# E-14_ENET1.net
KiCad netlist of a schematic drawn in Altium Designer
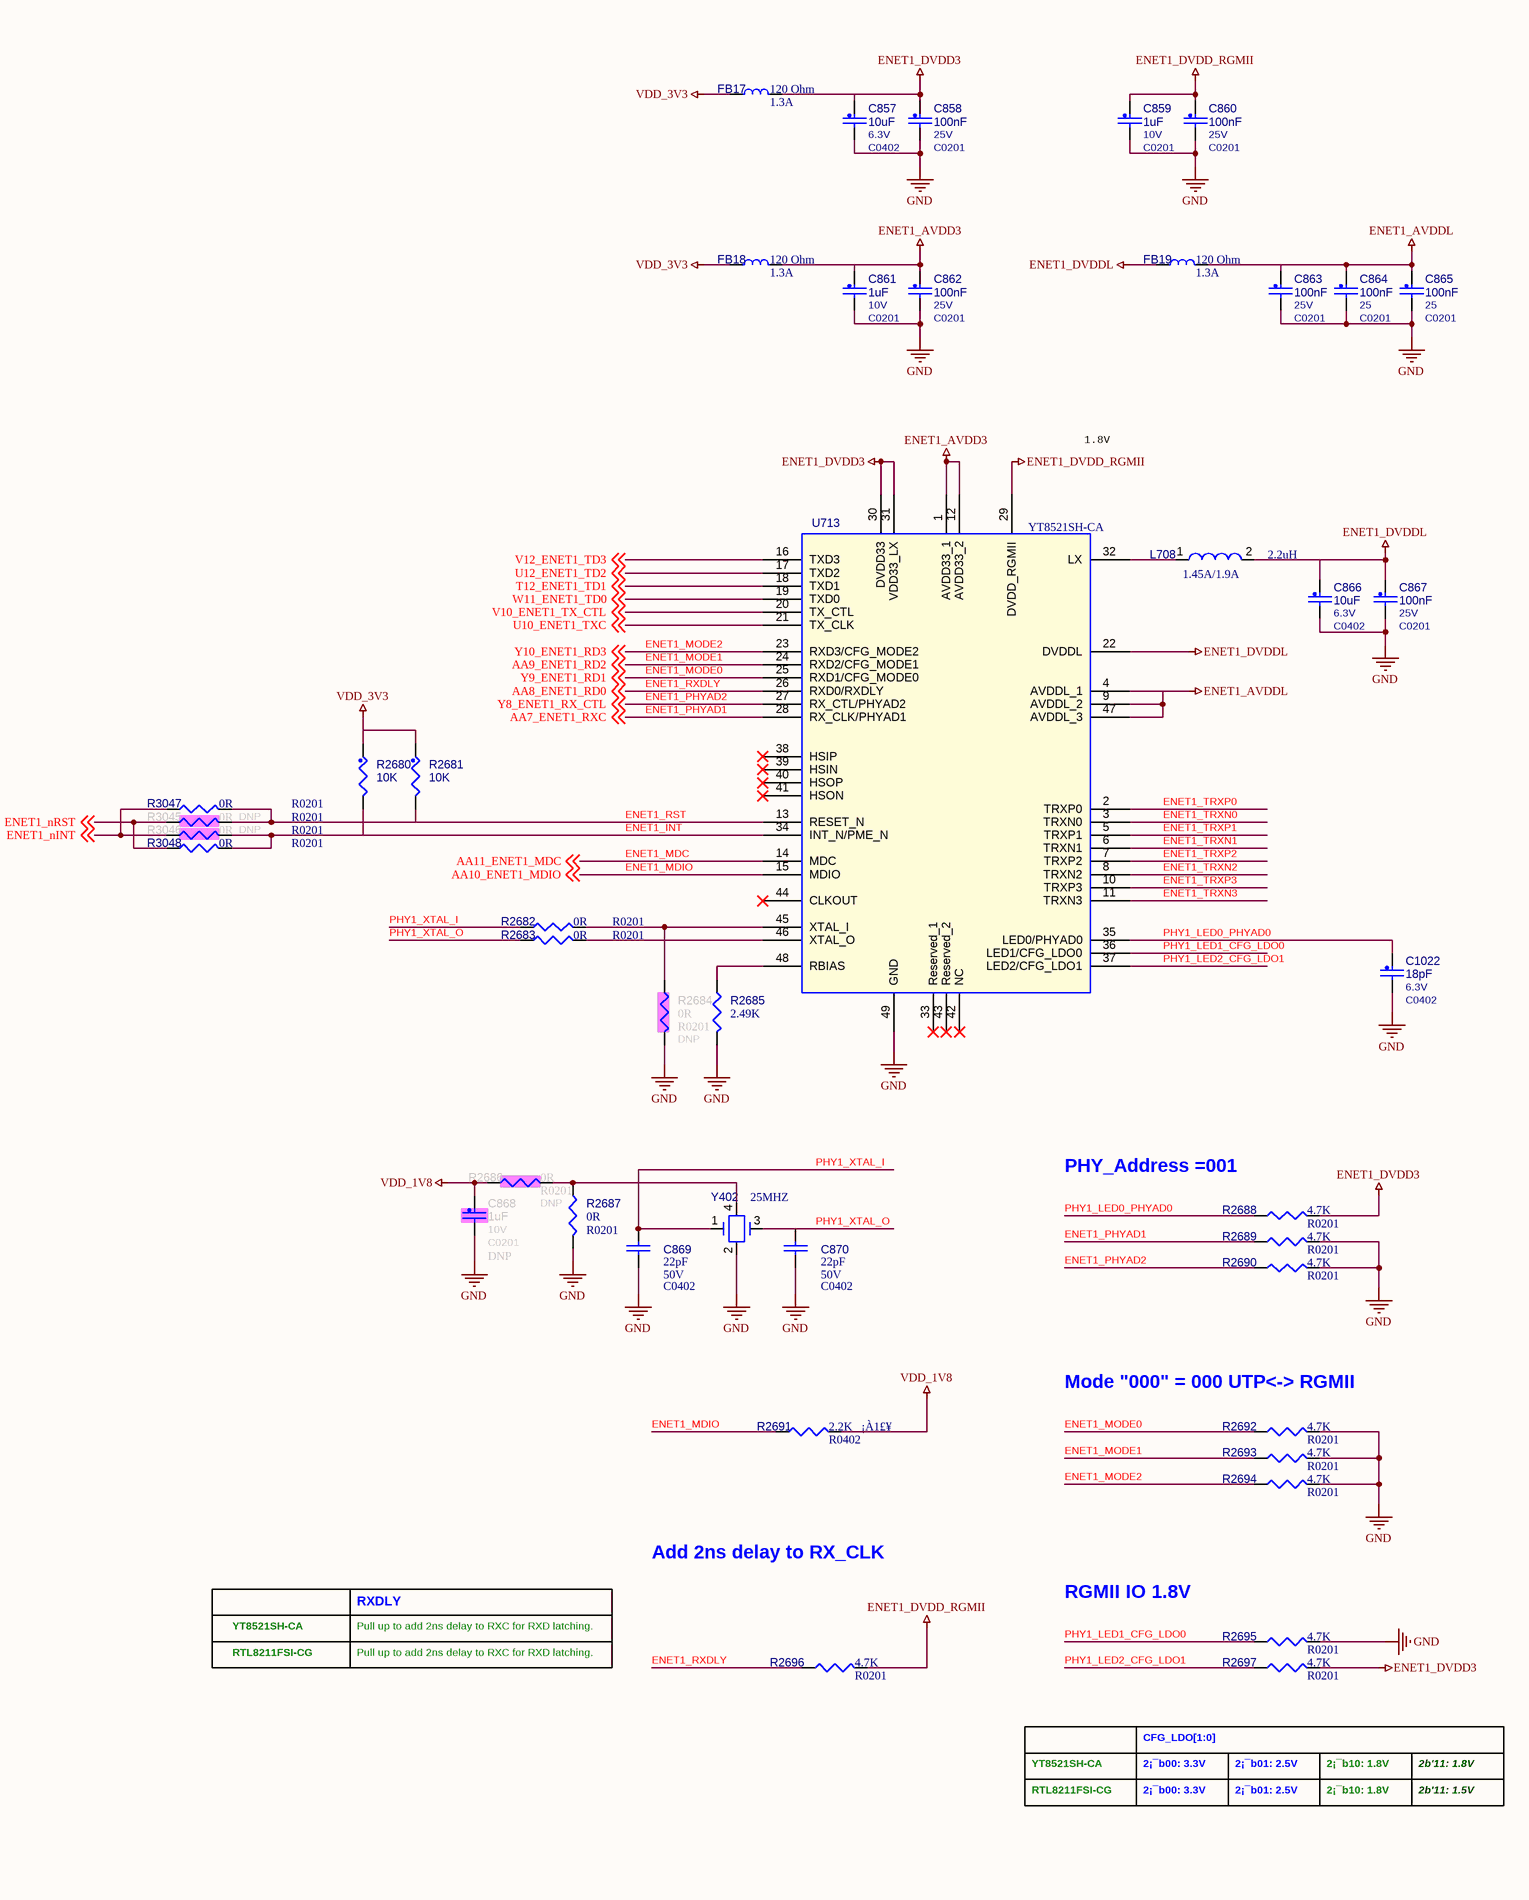
[diagram p0: E-14 ENET1.SchDoc, left]
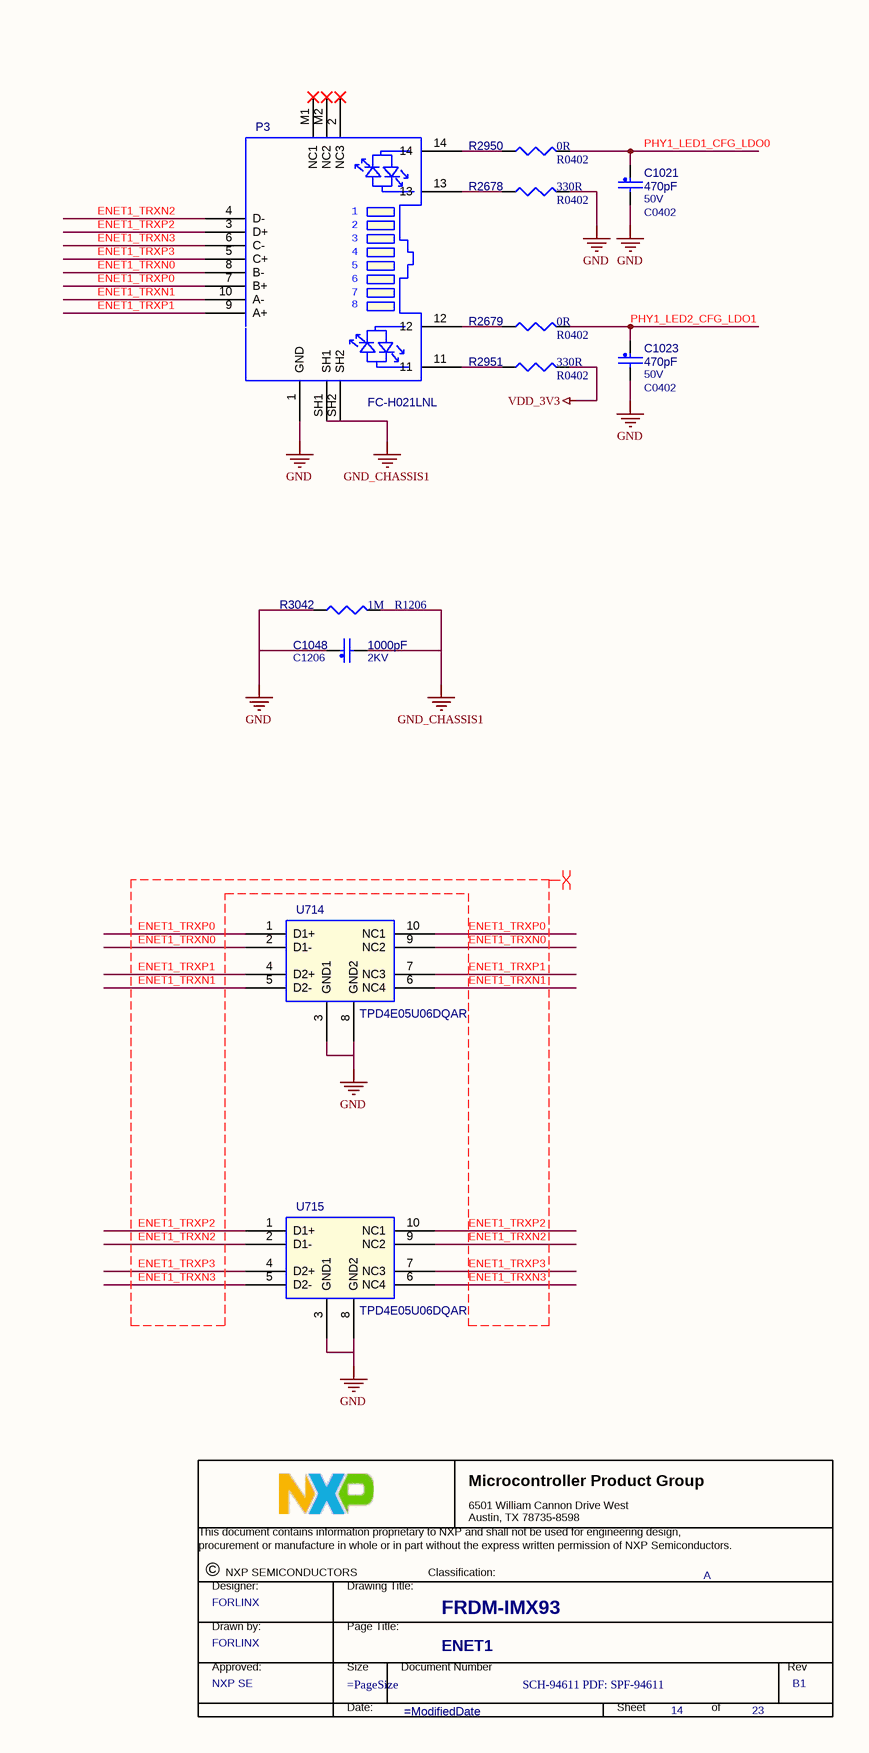
[diagram p1: E-14 ENET1.SchDoc, right]

(export (version "E")
  (design (tool "Eeschema 10.0.6"))
  (components
    (comp (ref "C857")
      (value "10uF")
      (footprint "C0402")
      (description "0402,10uF,6.3V,+/-20%,X5R")
      (fields
        (field (name "TOLERANCE") "20%")
        (field (name "VOLTAGE") "6.3V")
        (field (name "PCB FOOTPRINT") "C0402")
      )
      (libsource (lib "*") (part "CAP_NP"))
    )
    (comp (ref "C858")
      (value "100nF")
      (footprint "C0201")
      (description "0201,100nF,25V,+/-10%,X5R")
      (fields
        (field (name "VOLTAGE") "25V")
        (field (name "TOLERANCE") "20%")
        (field (name "PCB FOOTPRINT") "C0201")
      )
      (libsource (lib "*") (part "CAP_NP"))
    )
    (comp (ref "C859")
      (value "1uF")
      (footprint "C0201")
      (description "0201,1uF,10V,+/-20%,X5R")
      (fields
        (field (name "VOLTAGE") "10V")
        (field (name "TOLERANCE") "20%")
        (field (name "PCB FOOTPRINT") "C0201")
      )
      (libsource (lib "*") (part "CAP_NP"))
    )
    (comp (ref "C860")
      (value "100nF")
      (footprint "C0201")
      (description "0201,100nF,25V,+/-10%,X5R")
      (fields
        (field (name "TOLERANCE") "20%")
        (field (name "VOLTAGE") "25V")
        (field (name "PCB FOOTPRINT") "C0201")
      )
      (libsource (lib "*") (part "CAP_NP"))
    )
    (comp (ref "C861")
      (value "1uF")
      (footprint "C0201")
      (description "0201,1uF,10V,+/-20%,X5R")
      (fields
        (field (name "TOLERANCE") "20%")
        (field (name "VOLTAGE") "10V")
        (field (name "PCB FOOTPRINT") "C0201")
      )
      (libsource (lib "*") (part "CAP_NP"))
    )
    (comp (ref "C862")
      (value "100nF")
      (footprint "C0201")
      (description "0201,100nF,25V,+/-10%,X5R")
      (fields
        (field (name "TOLERANCE") "20%")
        (field (name "VOLTAGE") "25V")
        (field (name "PCB FOOTPRINT") "C0201")
      )
      (libsource (lib "*") (part "CAP_NP"))
    )
    (comp (ref "C863")
      (value "100nF")
      (footprint "C0201")
      (description "0201,100nF,25V,+/-10%,X5R")
      (fields
        (field (name "VOLTAGE") "25V")
        (field (name "TOLERANCE") "20%")
        (field (name "PCB FOOTPRINT") "C0201")
      )
      (libsource (lib "*") (part "CAP_NP"))
    )
    (comp (ref "C864")
      (value "100nF")
      (footprint "C0201")
      (description "0201,100nF,25V,+/-10%,X5R")
      (fields
        (field (name "VOLTAGE") "25")
        (field (name "TOLERANCE") "20%")
        (field (name "PCB FOOTPRINT") "C0201")
      )
      (libsource (lib "*") (part "CAP_NP"))
    )
    (comp (ref "C865")
      (value "100nF")
      (footprint "C0201")
      (description "0201,100nF,25V,+/-10%,X5R")
      (fields
        (field (name "TOLERANCE") "20%")
        (field (name "VOLTAGE") "25")
        (field (name "PCB FOOTPRINT") "C0201")
      )
      (libsource (lib "*") (part "CAP_NP"))
    )
    (comp (ref "C866")
      (value "10uF")
      (footprint "C0402")
      (description "0402,10uF,6.3V,+/-20%,X5R")
      (fields
        (field (name "VOLTAGE") "6.3V")
        (field (name "TOLERANCE") "20%")
        (field (name "PCB FOOTPRINT") "C0402")
      )
      (libsource (lib "*") (part "CAP_NP"))
    )
    (comp (ref "C867")
      (value "100nF")
      (footprint "C0201")
      (description "0201,100nF,25V,+/-10%,X5R")
      (fields
        (field (name "TOLERANCE") "20%")
        (field (name "VOLTAGE") "25V")
        (field (name "PCB FOOTPRINT") "C0201")
      )
      (libsource (lib "*") (part "CAP_NP"))
    )
    (comp (ref "C868")
      (value "1uF")
      (footprint "C0201")
      (description "0201,1uF,10V,+/-20%,X5R")
      (fields
        (field (name "ASSY_OPT") "DNP")
        (field (name "TOLERANCE") "20%")
        (field (name "VOLTAGE") "10V")
        (field (name "PCB FOOTPRINT") "C0201")
      )
      (libsource (lib "*") (part "CAP_NP"))
    )
    (comp (ref "C869")
      (value "22pF")
      (footprint "C0402")
      (description "0402,22pF,50V,+/-5%,NPO")
      (fields (field (name "PCB FOOTPRINT") "C0402") (field (name "VOLTAGE") "50V"))
      (libsource (lib "*") (part "C0402,22pF"))
    )
    (comp (ref "C870")
      (value "22pF")
      (footprint "C0402")
      (description "0402,22pF,50V,+/-5%,NPO")
      (fields (field (name "PCB FOOTPRINT") "C0402") (field (name "VOLTAGE") "50V"))
      (libsource (lib "*") (part "C0402,22pF"))
    )
    (comp (ref "C1021")
      (value "470pF")
      (footprint "C0402")
      (description "0402,470pF,50V,+/-5%,NPO")
      (fields
        (field (name "VOLTAGE") "50V")
        (field (name "TOLERANCE") "20%")
        (field (name "PCB FOOTPRINT") "C0402")
      )
      (libsource (lib "*") (part "CAP_NP"))
    )
    (comp (ref "C1022")
      (value "18pF")
      (footprint "C0402")
      (description "0402,18pF,50V,+/-5%,NPO")
      (fields
        (field (name "TOLERANCE") "20%")
        (field (name "VOLTAGE") "6.3V")
        (field (name "PCB FOOTPRINT") "C0402")
      )
      (libsource (lib "*") (part "CAP_NP"))
    )
    (comp (ref "C1023")
      (value "470pF")
      (footprint "C0402")
      (description "0402,470pF,50V,+/-5%,NPO")
      (fields
        (field (name "VOLTAGE") "50V")
        (field (name "TOLERANCE") "20%")
        (field (name "PCB FOOTPRINT") "C0402")
      )
      (libsource (lib "*") (part "CAP_NP"))
    )
    (comp (ref "C1048")
      (value "1000pF")
      (footprint "C1206")
      (description "1206,1nF,2KV,+/-10%")
      (fields
        (field (name "TOLERANCE") "20%")
        (field (name "VOLTAGE") "2KV")
        (field (name "PCB FOOTPRINT") "C1206")
      )
      (libsource (lib "*") (part "CAP_NP"))
    )
    (comp (ref "FB17")
      (value "120 Ohm")
      (footprint "FB0402")
      (description "0402,120Ohm@100MHz,2A")
      (fields (field (name "ELECTRIC CURRENT") "1.3A"))
      (libsource (lib "*") (part "FB0402,120ohm,1.3A"))
    )
    (comp (ref "FB18")
      (value "120 Ohm")
      (footprint "FB0402")
      (description "0402,120Ohm@100MHz,2A")
      (fields (field (name "ELECTRIC CURRENT") "1.3A"))
      (libsource (lib "*") (part "FB0402,120ohm,1.3A"))
    )
    (comp (ref "FB19")
      (value "120 Ohm")
      (footprint "FB0402")
      (description "0402,120Ohm@100MHz,2A")
      (fields (field (name "ELECTRIC CURRENT") "1.3A"))
      (libsource (lib "*") (part "FB0402,120ohm,1.3A"))
    )
    (comp (ref "L708")
      (value "2.2uH")
      (footprint "IND_2016A")
      (description "2.2uH,2*1.6*1mm,2.15A")
      (fields (field (name "ELECTRIC CURRENT") "1.45A/1.9A"))
      (libsource (lib "*") (part "INDUCTOR-WPN201612HR47MT"))
    )
    (comp (ref "P3")
      (value "FC-H021LNL")
      (footprint "RJ45-Gigabit")
      (description "HR851178A,RJ45,1000M")
      (libsource (lib "*") (part "FC-H021LNL_2"))
    )
    (comp (ref "R2678")
      (value "330R")
      (footprint "R0402")
      (description "0402,330Ohm,+/-1%")
      (fields (field (name "PCB FOOTPRINT") "R0402"))
      (libsource (lib "*") (part "R0402,4.7K_Dup1"))
    )
    (comp (ref "R2679")
      (value "0R")
      (footprint "R0402")
      (description "0402,0Ohm,+/-1%")
      (fields (field (name "PCB FOOTPRINT") "R0402"))
      (libsource (lib "*") (part "R0402,4.7K_Dup1"))
    )
    (comp (ref "R2680")
      (value "10K")
      (footprint "R0201")
      (description "0201,10K,+/-5%")
      (fields (field (name "TOLERANCE") "5%"))
      (libsource (lib "*") (part "RES"))
    )
    (comp (ref "R2681")
      (value "10K")
      (footprint "R0201")
      (description "0201,10K,+/-5%")
      (fields (field (name "TOLERANCE") "5%"))
      (libsource (lib "*") (part "RES"))
    )
    (comp (ref "R2682")
      (value "0R")
      (footprint "R0201")
      (description "0201,0Ohm,+/-5%")
      (fields (field (name "PCB FOOTPRINT") "R0201"))
      (libsource (lib "*") (part "R0402,1.5K"))
    )
    (comp (ref "R2683")
      (value "0R")
      (footprint "R0201")
      (description "0201,0Ohm,+/-5%")
      (fields (field (name "PCB FOOTPRINT") "R0201"))
      (libsource (lib "*") (part "R0402,1.5K"))
    )
    (comp (ref "R2684")
      (value "0R")
      (footprint "R0201")
      (description "0201,0Ohm,+/-5%")
      (fields (field (name "PCB FOOTPRINT") "R0201") (field (name "ASSY_OPT") "DNP"))
      (libsource (lib "*") (part "R0402,1.5K"))
    )
    (comp (ref "R2685")
      (value "2.49K")
      (footprint "R0402")
      (description "0402,2.49K,+/-1%")
      (libsource (lib "*") (part "R0402,2.49K"))
    )
    (comp (ref "R2686")
      (value "0R")
      (footprint "R0201")
      (description "0201,0Ohm,+/-5%")
      (fields (field (name "PCB FOOTPRINT") "R0201") (field (name "ASSY_OPT") "DNP"))
      (libsource (lib "*") (part "R0402,1.5K"))
    )
    (comp (ref "R2687")
      (value "0R")
      (footprint "R0201")
      (description "0201,0Ohm,+/-5%")
      (fields (field (name "PCB FOOTPRINT") "R0201"))
      (libsource (lib "*") (part "R0402,1.5K"))
    )
    (comp (ref "R2688")
      (value "4.7K")
      (footprint "R0201")
      (description "0201,4.7K,+/-1%")
      (fields (field (name "PCB FOOTPRINT") "R0201"))
      (libsource (lib "*") (part "R0402,4.7K_Dup1"))
    )
    (comp (ref "R2689")
      (value "4.7K")
      (footprint "R0201")
      (description "0201,4.7K,+/-1%")
      (fields (field (name "PCB FOOTPRINT") "R0201"))
      (libsource (lib "*") (part "R0402,4.7K_Dup1"))
    )
    (comp (ref "R2690")
      (value "4.7K")
      (footprint "R0201")
      (description "0201,4.7K,+/-1%")
      (fields (field (name "PCB FOOTPRINT") "R0201"))
      (libsource (lib "*") (part "R0402,4.7K_Dup1"))
    )
    (comp (ref "R2691")
      (value "2.2K")
      (footprint "R0402")
      (description "0402,2.2K,+/-1%")
      (fields (field (name "PRECISION") "±1％") (field (name "PCB FOOTPRINT") "R0402"))
      (libsource (lib "*") (part "R0402,1.5K"))
    )
    (comp (ref "R2692")
      (value "4.7K")
      (footprint "R0201")
      (description "0201,4.7K,+/-1%")
      (fields (field (name "PCB FOOTPRINT") "R0201"))
      (libsource (lib "*") (part "R0402,4.7K_Dup1"))
    )
    (comp (ref "R2693")
      (value "4.7K")
      (footprint "R0201")
      (description "0201,4.7K,+/-1%")
      (fields (field (name "PCB FOOTPRINT") "R0201"))
      (libsource (lib "*") (part "R0402,4.7K_Dup1"))
    )
    (comp (ref "R2694")
      (value "4.7K")
      (footprint "R0201")
      (description "0201,4.7K,+/-1%")
      (fields (field (name "PCB FOOTPRINT") "R0201"))
      (libsource (lib "*") (part "R0402,4.7K_Dup1"))
    )
    (comp (ref "R2695")
      (value "4.7K")
      (footprint "R0201")
      (description "0201,4.7K,+/-1%")
      (fields (field (name "PCB FOOTPRINT") "R0201"))
      (libsource (lib "*") (part "R0402,4.7K_Dup1"))
    )
    (comp (ref "R2696")
      (value "4.7K")
      (footprint "R0201")
      (description "0201,4.7K,+/-1%")
      (fields (field (name "PCB FOOTPRINT") "R0201"))
      (libsource (lib "*") (part "R0402,4.7K_Dup1"))
    )
    (comp (ref "R2697")
      (value "4.7K")
      (footprint "R0201")
      (description "0201,4.7K,+/-1%")
      (fields (field (name "PCB FOOTPRINT") "R0201"))
      (libsource (lib "*") (part "R0402,4.7K_Dup1"))
    )
    (comp (ref "R2950")
      (value "0R")
      (footprint "R0402")
      (description "0402,0Ohm,+/-1%")
      (fields (field (name "PCB FOOTPRINT") "R0402"))
      (libsource (lib "*") (part "R0402,4.7K_Dup1"))
    )
    (comp (ref "R2951")
      (value "330R")
      (footprint "R0402")
      (description "0402,330Ohm,+/-1%")
      (fields (field (name "PCB FOOTPRINT") "R0402"))
      (libsource (lib "*") (part "R0402,4.7K_Dup1"))
    )
    (comp (ref "R3042")
      (value "1M")
      (footprint "R1206")
      (description "1206,1M,+/-5%")
      (fields (field (name "PCB FOOTPRINT") "R1206"))
      (libsource (lib "*") (part "R0402,4.7K_Dup1"))
    )
    (comp (ref "R3045")
      (value "0R")
      (footprint "R0201")
      (description "0201,0Ohm,+/-5%")
      (fields (field (name "PCB FOOTPRINT") "R0201") (field (name "ASSY_OPT") "DNP"))
      (libsource (lib "*") (part "R0402,1.5K"))
    )
    (comp (ref "R3046")
      (value "0R")
      (footprint "R0201")
      (description "0201,0Ohm,+/-5%")
      (fields (field (name "PCB FOOTPRINT") "R0201") (field (name "ASSY_OPT") "DNP"))
      (libsource (lib "*") (part "R0402,1.5K"))
    )
    (comp (ref "R3047")
      (value "0R")
      (footprint "R0201")
      (description "0201,0Ohm,+/-5%")
      (fields (field (name "PCB FOOTPRINT") "R0201"))
      (libsource (lib "*") (part "R0402,1.5K"))
    )
    (comp (ref "R3048")
      (value "0R")
      (footprint "R0201")
      (description "0201,0Ohm,+/-5%")
      (fields (field (name "PCB FOOTPRINT") "R0201"))
      (libsource (lib "*") (part "R0402,1.5K"))
    )
    (comp (ref "U713")
      (value "YT8521SH-CA")
      (footprint "QFN48P_0_4BSC_6x6_H")
      (libsource (lib "*") (part "YT8521SH-CA"))
    )
    (comp (ref "U714")
      (value "TPD4E05U06DQAR")
      (footprint "USON-10")
      (description "TPD4E05U06DQAR,USON")
      (libsource (lib "*") (part "TPD4E05U06DQAR_6"))
    )
    (comp (ref "U715")
      (value "TPD4E05U06DQAR")
      (footprint "USON-10")
      (description "TPD4E05U06DQAR,USON")
      (libsource (lib "*") (part "TPD4E05U06DQAR_7"))
    )
    (comp (ref "Y402")
      (value "25MHZ")
      (footprint "xtlosc4_3p2x2p5mm_sm")
      (description "Crystal,25MHZ,4P,3.2*2.5mm,+/-20ppm,20pf")
      (libsource (lib "*") (part "CRYSTAL_4P-TSX-3225"))
    )
  )
  (nets
    (net (code "1") (name "/ENET1_INT") (class "Default")
      (node (ref "R2680") (pin "2") (pinfunction "2_2") (pintype "passive"))
      (node (ref "R3046") (pin "2") (pinfunction "2_2") (pintype "passive"))
      (node (ref "R3048") (pin "2") (pinfunction "2_2") (pintype "passive"))
      (node (ref "U713") (pin "34") (pinfunction "INT_N/PME_N_34") (pintype "passive"))
    )
    (net (code "2") (name "/ENET1_RST") (class "Default")
      (node (ref "R2681") (pin "2") (pinfunction "2_2") (pintype "passive"))
      (node (ref "R3045") (pin "2") (pinfunction "2_2") (pintype "passive"))
      (node (ref "R3047") (pin "2") (pinfunction "2_2") (pintype "passive"))
      (node (ref "U713") (pin "13") (pinfunction "RESET_N_13") (pintype "passive"))
    )
    (net (code "3") (name "/ENET1_TRXN0") (class "Default")
      (node (ref "P3") (pin "8") (pinfunction "B-_8") (pintype "passive"))
      (node (ref "U713") (pin "3") (pinfunction "TRXN0_3") (pintype "passive"))
      (node (ref "U714") (pin "2") (pinfunction "D1-_2") (pintype "passive"))
      (node (ref "U714") (pin "9") (pinfunction "NC2_9") (pintype "passive"))
    )
    (net (code "4") (name "/ENET1_TRXN1") (class "Default")
      (node (ref "P3") (pin "10") (pinfunction "A-_10") (pintype "passive"))
      (node (ref "U713") (pin "6") (pinfunction "TRXN1_6") (pintype "passive"))
      (node (ref "U714") (pin "5") (pinfunction "D2-_5") (pintype "passive"))
      (node (ref "U714") (pin "6") (pinfunction "NC4_6") (pintype "passive"))
    )
    (net (code "5") (name "/ENET1_TRXN2") (class "Default")
      (node (ref "P3") (pin "4") (pinfunction "D-_4") (pintype "passive"))
      (node (ref "U713") (pin "8") (pinfunction "TRXN2_8") (pintype "passive"))
      (node (ref "U715") (pin "2") (pinfunction "D1-_2") (pintype "passive"))
      (node (ref "U715") (pin "9") (pinfunction "NC2_9") (pintype "passive"))
    )
    (net (code "6") (name "/ENET1_TRXN3") (class "Default")
      (node (ref "P3") (pin "6") (pinfunction "C-_6") (pintype "passive"))
      (node (ref "U713") (pin "11") (pinfunction "TRXN3_11") (pintype "passive"))
      (node (ref "U715") (pin "5") (pinfunction "D2-_5") (pintype "passive"))
      (node (ref "U715") (pin "6") (pinfunction "NC4_6") (pintype "passive"))
    )
    (net (code "7") (name "/ENET1_TRXP0") (class "Default")
      (node (ref "P3") (pin "7") (pinfunction "B+_7") (pintype "passive"))
      (node (ref "U713") (pin "2") (pinfunction "TRXP0_2") (pintype "passive"))
      (node (ref "U714") (pin "1") (pinfunction "D1+_1") (pintype "passive"))
      (node (ref "U714") (pin "10") (pinfunction "NC1_10") (pintype "passive"))
    )
    (net (code "8") (name "/ENET1_TRXP1") (class "Default")
      (node (ref "P3") (pin "9") (pinfunction "A+_9") (pintype "passive"))
      (node (ref "U713") (pin "5") (pinfunction "TRXP1_5") (pintype "passive"))
      (node (ref "U714") (pin "4") (pinfunction "D2+_4") (pintype "passive"))
      (node (ref "U714") (pin "7") (pinfunction "NC3_7") (pintype "passive"))
    )
    (net (code "9") (name "/ENET1_TRXP2") (class "Default")
      (node (ref "P3") (pin "3") (pinfunction "D+_3") (pintype "passive"))
      (node (ref "U713") (pin "7") (pinfunction "TRXP2_7") (pintype "passive"))
      (node (ref "U715") (pin "1") (pinfunction "D1+_1") (pintype "passive"))
      (node (ref "U715") (pin "10") (pinfunction "NC1_10") (pintype "passive"))
    )
    (net (code "10") (name "/ENET1_TRXP3") (class "Default")
      (node (ref "P3") (pin "5") (pinfunction "C+_5") (pintype "passive"))
      (node (ref "U713") (pin "10") (pinfunction "TRXP3_10") (pintype "passive"))
      (node (ref "U715") (pin "4") (pinfunction "D2+_4") (pintype "passive"))
      (node (ref "U715") (pin "7") (pinfunction "NC3_7") (pintype "passive"))
    )
    (net (code "11") (name "/PHY1_LED0_PHYAD0") (class "Default")
      (node (ref "C1022") (pin "1") (pinfunction "1_1") (pintype "passive"))
      (node (ref "R2688") (pin "1") (pinfunction "1_1") (pintype "passive"))
      (node (ref "U713") (pin "35") (pinfunction "LED0/PHYAD0_35") (pintype "passive"))
    )
    (net (code "12") (name "/PHY1_LED1_CFG_LDO0") (class "Default")
      (node (ref "C1021") (pin "1") (pinfunction "1_1") (pintype "passive"))
      (node (ref "R2695") (pin "1") (pinfunction "1_1") (pintype "passive"))
      (node (ref "R2950") (pin "2") (pinfunction "2_2") (pintype "passive"))
      (node (ref "U713") (pin "36") (pinfunction "LED1/CFG_LDO0_36") (pintype "passive"))
    )
    (net (code "13") (name "/PHY1_LED2_CFG_LDO1") (class "Default")
      (node (ref "C1023") (pin "1") (pinfunction "1_1") (pintype "passive"))
      (node (ref "R2679") (pin "2") (pinfunction "2_2") (pintype "passive"))
      (node (ref "R2697") (pin "1") (pinfunction "1_1") (pintype "passive"))
      (node (ref "U713") (pin "37") (pinfunction "LED2/CFG_LDO1_37") (pintype "passive"))
    )
    (net (code "14") (name "/PHY1_XTAL_I") (class "Default")
      (node (ref "C869") (pin "1") (pinfunction "1_1") (pintype "passive"))
      (node (ref "R2682") (pin "1") (pinfunction "1_1") (pintype "passive"))
      (node (ref "Y402") (pin "1") (pinfunction "1_1") (pintype "passive"))
    )
    (net (code "15") (name "/PHY1_XTAL_O") (class "Default")
      (node (ref "C870") (pin "1") (pinfunction "1_1") (pintype "passive"))
      (node (ref "R2683") (pin "1") (pinfunction "1_1") (pintype "passive"))
      (node (ref "Y402") (pin "3") (pinfunction "3_3") (pintype "passive"))
    )
    (net (code "16") (name "AA7_ENET1_RXC") (class "Default")
      (node (ref "R2689") (pin "1") (pinfunction "1_1") (pintype "passive"))
      (node (ref "U713") (pin "28") (pinfunction "RX_CLK/PHYAD1_28") (pintype "passive"))
    )
    (net (code "17") (name "AA8_ENET1_RD0") (class "Default")
      (node (ref "R2696") (pin "1") (pinfunction "1_1") (pintype "passive"))
      (node (ref "U713") (pin "26") (pinfunction "RXD0/RXDLY_26") (pintype "passive"))
    )
    (net (code "18") (name "AA9_ENET1_RD2") (class "Default")
      (node (ref "R2693") (pin "1") (pinfunction "1_1") (pintype "passive"))
      (node (ref "U713") (pin "24") (pinfunction "RXD2/CFG_MODE1_24") (pintype "passive"))
    )
    (net (code "19") (name "AA10_ENET1_MDIO") (class "Default")
      (node (ref "R2691") (pin "1") (pinfunction "1_1") (pintype "passive"))
      (node (ref "U713") (pin "15") (pinfunction "MDIO_15") (pintype "passive"))
    )
    (net (code "20") (name "AA11_ENET1_MDC") (class "Default")
      (node (ref "U713") (pin "14") (pinfunction "MDC_14") (pintype "passive"))
    )
    (net (code "21") (name "ENET1_AVDD3") (class "Default")
      (node (ref "C861") (pin "1") (pinfunction "1_1") (pintype "passive"))
      (node (ref "C862") (pin "1") (pinfunction "1_1") (pintype "passive"))
      (node (ref "FB18") (pin "2") (pinfunction "2_2") (pintype "passive"))
      (node (ref "U713") (pin "1") (pinfunction "AVDD33_1_1") (pintype "passive"))
      (node (ref "U713") (pin "12") (pinfunction "AVDD33_2_12") (pintype "passive"))
    )
    (net (code "22") (name "ENET1_AVDDL") (class "Default")
      (node (ref "C863") (pin "1") (pinfunction "1_1") (pintype "passive"))
      (node (ref "C864") (pin "1") (pinfunction "1_1") (pintype "passive"))
      (node (ref "C865") (pin "1") (pinfunction "1_1") (pintype "passive"))
      (node (ref "FB19") (pin "2") (pinfunction "2_2") (pintype "passive"))
      (node (ref "U713") (pin "4") (pinfunction "AVDDL_1_4") (pintype "passive"))
      (node (ref "U713") (pin "47") (pinfunction "AVDDL_3_47") (pintype "passive"))
      (node (ref "U713") (pin "9") (pinfunction "AVDDL_2_9") (pintype "passive"))
    )
    (net (code "23") (name "ENET1_DVDD3") (class "Default")
      (node (ref "C857") (pin "1") (pinfunction "1_1") (pintype "passive"))
      (node (ref "C858") (pin "1") (pinfunction "1_1") (pintype "passive"))
      (node (ref "FB17") (pin "2") (pinfunction "2_2") (pintype "passive"))
      (node (ref "R2688") (pin "2") (pinfunction "2_2") (pintype "passive"))
      (node (ref "R2697") (pin "2") (pinfunction "2_2") (pintype "passive"))
      (node (ref "U713") (pin "30") (pinfunction "DVDD33_30") (pintype "passive"))
      (node (ref "U713") (pin "31") (pinfunction "VDD33_LX_31") (pintype "passive"))
    )
    (net (code "24") (name "ENET1_DVDDL") (class "Default")
      (node (ref "C866") (pin "1") (pinfunction "1_1") (pintype "passive"))
      (node (ref "C867") (pin "1") (pinfunction "1_1") (pintype "passive"))
      (node (ref "FB19") (pin "1") (pinfunction "1_1") (pintype "passive"))
      (node (ref "L708") (pin "2") (pinfunction "2_2") (pintype "passive"))
      (node (ref "U713") (pin "22") (pinfunction "DVDDL_22") (pintype "passive"))
    )
    (net (code "25") (name "ENET1_DVDD_RGMII") (class "Default")
      (node (ref "C859") (pin "1") (pinfunction "1_1") (pintype "passive"))
      (node (ref "C860") (pin "1") (pinfunction "1_1") (pintype "passive"))
      (node (ref "R2696") (pin "2") (pinfunction "2_2") (pintype "passive"))
      (node (ref "U713") (pin "29") (pinfunction "DVDD_RGMII_29") (pintype "passive"))
    )
    (net (code "26") (name "ENET1_nINT") (class "Default")
      (node (ref "R3046") (pin "1") (pinfunction "1_1") (pintype "passive"))
      (node (ref "R3047") (pin "1") (pinfunction "1_1") (pintype "passive"))
    )
    (net (code "27") (name "ENET1_nRST") (class "Default")
      (node (ref "R3045") (pin "1") (pinfunction "1_1") (pintype "passive"))
      (node (ref "R3048") (pin "1") (pinfunction "1_1") (pintype "passive"))
    )
    (net (code "28") (name "GND") (class "Default")
      (node (ref "C1021") (pin "2") (pinfunction "2_2") (pintype "passive"))
      (node (ref "C1022") (pin "2") (pinfunction "2_2") (pintype "passive"))
      (node (ref "C1023") (pin "2") (pinfunction "2_2") (pintype "passive"))
      (node (ref "C1048") (pin "1") (pinfunction "1_1") (pintype "passive"))
      (node (ref "C857") (pin "2") (pinfunction "2_2") (pintype "passive"))
      (node (ref "C858") (pin "2") (pinfunction "2_2") (pintype "passive"))
      (node (ref "C859") (pin "2") (pinfunction "2_2") (pintype "passive"))
      (node (ref "C860") (pin "2") (pinfunction "2_2") (pintype "passive"))
      (node (ref "C861") (pin "2") (pinfunction "2_2") (pintype "passive"))
      (node (ref "C862") (pin "2") (pinfunction "2_2") (pintype "passive"))
      (node (ref "C863") (pin "2") (pinfunction "2_2") (pintype "passive"))
      (node (ref "C864") (pin "2") (pinfunction "2_2") (pintype "passive"))
      (node (ref "C865") (pin "2") (pinfunction "2_2") (pintype "passive"))
      (node (ref "C866") (pin "2") (pinfunction "2_2") (pintype "passive"))
      (node (ref "C867") (pin "2") (pinfunction "2_2") (pintype "passive"))
      (node (ref "C868") (pin "2") (pinfunction "2_2") (pintype "passive"))
      (node (ref "C869") (pin "2") (pinfunction "2_2") (pintype "passive"))
      (node (ref "C870") (pin "2") (pinfunction "2_2") (pintype "passive"))
      (node (ref "P3") (pin "1") (pinfunction "GND_1") (pintype "power_in"))
      (node (ref "R2678") (pin "2") (pinfunction "2_2") (pintype "passive"))
      (node (ref "R2684") (pin "2") (pinfunction "2_2") (pintype "passive"))
      (node (ref "R2685") (pin "2") (pinfunction "2_2") (pintype "passive"))
      (node (ref "R2687") (pin "2") (pinfunction "2_2") (pintype "passive"))
      (node (ref "R2689") (pin "2") (pinfunction "2_2") (pintype "passive"))
      (node (ref "R2690") (pin "2") (pinfunction "2_2") (pintype "passive"))
      (node (ref "R2692") (pin "2") (pinfunction "2_2") (pintype "passive"))
      (node (ref "R2693") (pin "2") (pinfunction "2_2") (pintype "passive"))
      (node (ref "R2694") (pin "2") (pinfunction "2_2") (pintype "passive"))
      (node (ref "R2695") (pin "2") (pinfunction "2_2") (pintype "passive"))
      (node (ref "R3042") (pin "1") (pinfunction "1_1") (pintype "passive"))
      (node (ref "U713") (pin "49") (pinfunction "GND_49") (pintype "passive"))
      (node (ref "U714") (pin "3") (pinfunction "GND1_3") (pintype "passive"))
      (node (ref "U714") (pin "8") (pinfunction "GND2_8") (pintype "passive"))
      (node (ref "U715") (pin "3") (pinfunction "GND1_3") (pintype "passive"))
      (node (ref "U715") (pin "8") (pinfunction "GND2_8") (pintype "passive"))
      (node (ref "Y402") (pin "2") (pinfunction "2_2") (pintype "passive"))
    )
    (net (code "29") (name "GND_CHASSIS1") (class "Default")
      (node (ref "C1048") (pin "2") (pinfunction "2_2") (pintype "passive"))
      (node (ref "P3") (pin "SH1") (pinfunction "SH1_SH1") (pintype "passive"))
      (node (ref "P3") (pin "SH2") (pinfunction "SH2_SH2") (pintype "passive"))
      (node (ref "R3042") (pin "2") (pinfunction "2_2") (pintype "passive"))
    )
    (net (code "30") (name "Net-(P3-Pad11)") (class "Default")
      (node (ref "P3") (pin "11") (pinfunction "11_11") (pintype "passive"))
      (node (ref "R2951") (pin "1") (pinfunction "1_1") (pintype "passive"))
    )
    (net (code "31") (name "Net-(P3-Pad12)") (class "Default")
      (node (ref "P3") (pin "12") (pinfunction "12_12") (pintype "passive"))
      (node (ref "R2679") (pin "1") (pinfunction "1_1") (pintype "passive"))
    )
    (net (code "32") (name "Net-(P3-Pad13)") (class "Default")
      (node (ref "P3") (pin "13") (pinfunction "13_13") (pintype "passive"))
      (node (ref "R2678") (pin "1") (pinfunction "1_1") (pintype "passive"))
    )
    (net (code "33") (name "Net-(P3-Pad14)") (class "Default")
      (node (ref "P3") (pin "14") (pinfunction "14_14") (pintype "passive"))
      (node (ref "R2950") (pin "1") (pinfunction "1_1") (pintype "passive"))
    )
    (net (code "34") (name "Net-(R2686-Pad2)") (class "Default")
      (node (ref "R2686") (pin "2") (pinfunction "2_2") (pintype "passive"))
      (node (ref "R2687") (pin "1") (pinfunction "1_1") (pintype "passive"))
      (node (ref "Y402") (pin "4") (pinfunction "4_4") (pintype "passive"))
    )
    (net (code "35") (name "Net-(U713-LX)") (class "Default")
      (node (ref "L708") (pin "1") (pinfunction "1_1") (pintype "passive"))
      (node (ref "U713") (pin "32") (pinfunction "LX_32") (pintype "passive"))
    )
    (net (code "36") (name "Net-(U713-RBIAS)") (class "Default")
      (node (ref "R2685") (pin "1") (pinfunction "1_1") (pintype "passive"))
      (node (ref "U713") (pin "48") (pinfunction "RBIAS_48") (pintype "passive"))
    )
    (net (code "37") (name "Net-(U713-XTAL_I)") (class "Default")
      (node (ref "R2682") (pin "2") (pinfunction "2_2") (pintype "passive"))
      (node (ref "R2684") (pin "1") (pinfunction "1_1") (pintype "passive"))
      (node (ref "U713") (pin "45") (pinfunction "XTAL_I_45") (pintype "passive"))
    )
    (net (code "38") (name "Net-(U713-XTAL_O)") (class "Default")
      (node (ref "R2683") (pin "2") (pinfunction "2_2") (pintype "passive"))
      (node (ref "U713") (pin "46") (pinfunction "XTAL_O_46") (pintype "passive"))
    )
    (net (code "39") (name "T12_ENET1_TD1") (class "Default")
      (node (ref "U713") (pin "18") (pinfunction "TXD1_18") (pintype "passive"))
    )
    (net (code "40") (name "U10_ENET1_TXC") (class "Default")
      (node (ref "U713") (pin "21") (pinfunction "TX_CLK_21") (pintype "passive"))
    )
    (net (code "41") (name "U12_ENET1_TD2") (class "Default")
      (node (ref "U713") (pin "17") (pinfunction "TXD2_17") (pintype "passive"))
    )
    (net (code "42") (name "V10_ENET1_TX_CTL") (class "Default")
      (node (ref "U713") (pin "20") (pinfunction "TX_CTL_20") (pintype "passive"))
    )
    (net (code "43") (name "V12_ENET1_TD3") (class "Default")
      (node (ref "U713") (pin "16") (pinfunction "TXD3_16") (pintype "passive"))
    )
    (net (code "44") (name "VDD_1V8") (class "Default")
      (node (ref "C868") (pin "1") (pinfunction "1_1") (pintype "passive"))
      (node (ref "R2686") (pin "1") (pinfunction "1_1") (pintype "passive"))
      (node (ref "R2691") (pin "2") (pinfunction "2_2") (pintype "passive"))
    )
    (net (code "45") (name "VDD_3V3") (class "Default")
      (node (ref "FB17") (pin "1") (pinfunction "1_1") (pintype "passive"))
      (node (ref "FB18") (pin "1") (pinfunction "1_1") (pintype "passive"))
      (node (ref "R2680") (pin "1") (pinfunction "1_1") (pintype "passive"))
      (node (ref "R2681") (pin "1") (pinfunction "1_1") (pintype "passive"))
      (node (ref "R2951") (pin "2") (pinfunction "2_2") (pintype "passive"))
    )
    (net (code "46") (name "W11_ENET1_TD0") (class "Default")
      (node (ref "U713") (pin "19") (pinfunction "TXD0_19") (pintype "passive"))
    )
    (net (code "47") (name "Y8_ENET1_RX_CTL") (class "Default")
      (node (ref "R2690") (pin "1") (pinfunction "1_1") (pintype "passive"))
      (node (ref "U713") (pin "27") (pinfunction "RX_CTL/PHYAD2_27") (pintype "passive"))
    )
    (net (code "48") (name "Y9_ENET1_RD1") (class "Default")
      (node (ref "R2692") (pin "1") (pinfunction "1_1") (pintype "passive"))
      (node (ref "U713") (pin "25") (pinfunction "RXD1/CFG_MODE0_25") (pintype "passive"))
    )
    (net (code "49") (name "Y10_ENET1_RD3") (class "Default")
      (node (ref "R2694") (pin "1") (pinfunction "1_1") (pintype "passive"))
      (node (ref "U713") (pin "23") (pinfunction "RXD3/CFG_MODE2_23") (pintype "passive"))
    )
    (net (code "50") (name "unconnected-(P3-NC1-PadM1)") (class "Default")
      (node (ref "P3") (pin "M1") (pinfunction "NC1_M1") (pintype "passive+no_connect"))
    )
    (net (code "51") (name "unconnected-(P3-NC2-PadM2)") (class "Default")
      (node (ref "P3") (pin "M2") (pinfunction "NC2_M2") (pintype "passive+no_connect"))
    )
    (net (code "52") (name "unconnected-(P3-NC3-Pad2)") (class "Default")
      (node (ref "P3") (pin "2") (pinfunction "NC3_2") (pintype "passive+no_connect"))
    )
    (net (code "53") (name "unconnected-(U713-CLKOUT-Pad44)") (class "Default")
      (node (ref "U713") (pin "44") (pinfunction "CLKOUT_44") (pintype "passive+no_connect"))
    )
    (net (code "54") (name "unconnected-(U713-HSIN-Pad39)") (class "Default")
      (node (ref "U713") (pin "39") (pinfunction "HSIN_39") (pintype "passive+no_connect"))
    )
    (net (code "55") (name "unconnected-(U713-HSIP-Pad38)") (class "Default")
      (node (ref "U713") (pin "38") (pinfunction "HSIP_38") (pintype "passive+no_connect"))
    )
    (net (code "56") (name "unconnected-(U713-HSON-Pad41)") (class "Default")
      (node (ref "U713") (pin "41") (pinfunction "HSON_41") (pintype "passive+no_connect"))
    )
    (net (code "57") (name "unconnected-(U713-HSOP-Pad40)") (class "Default")
      (node (ref "U713") (pin "40") (pinfunction "HSOP_40") (pintype "passive+no_connect"))
    )
    (net (code "58") (name "unconnected-(U713-NC-Pad42)") (class "Default")
      (node (ref "U713") (pin "42") (pinfunction "NC_42") (pintype "passive+no_connect"))
    )
    (net (code "59") (name "unconnected-(U713-Reserved_1-Pad33)") (class "Default")
      (node (ref "U713") (pin "33") (pinfunction "Reserved_1_33") (pintype "passive+no_connect"))
    )
    (net (code "60") (name "unconnected-(U713-Reserved_2-Pad43)") (class "Default")
      (node (ref "U713") (pin "43") (pinfunction "Reserved_2_43") (pintype "passive+no_connect"))
    )
  )
)
